# ANIMA_Small_Scale.net
KiCad netlist of a schematic drawn in EAGLE
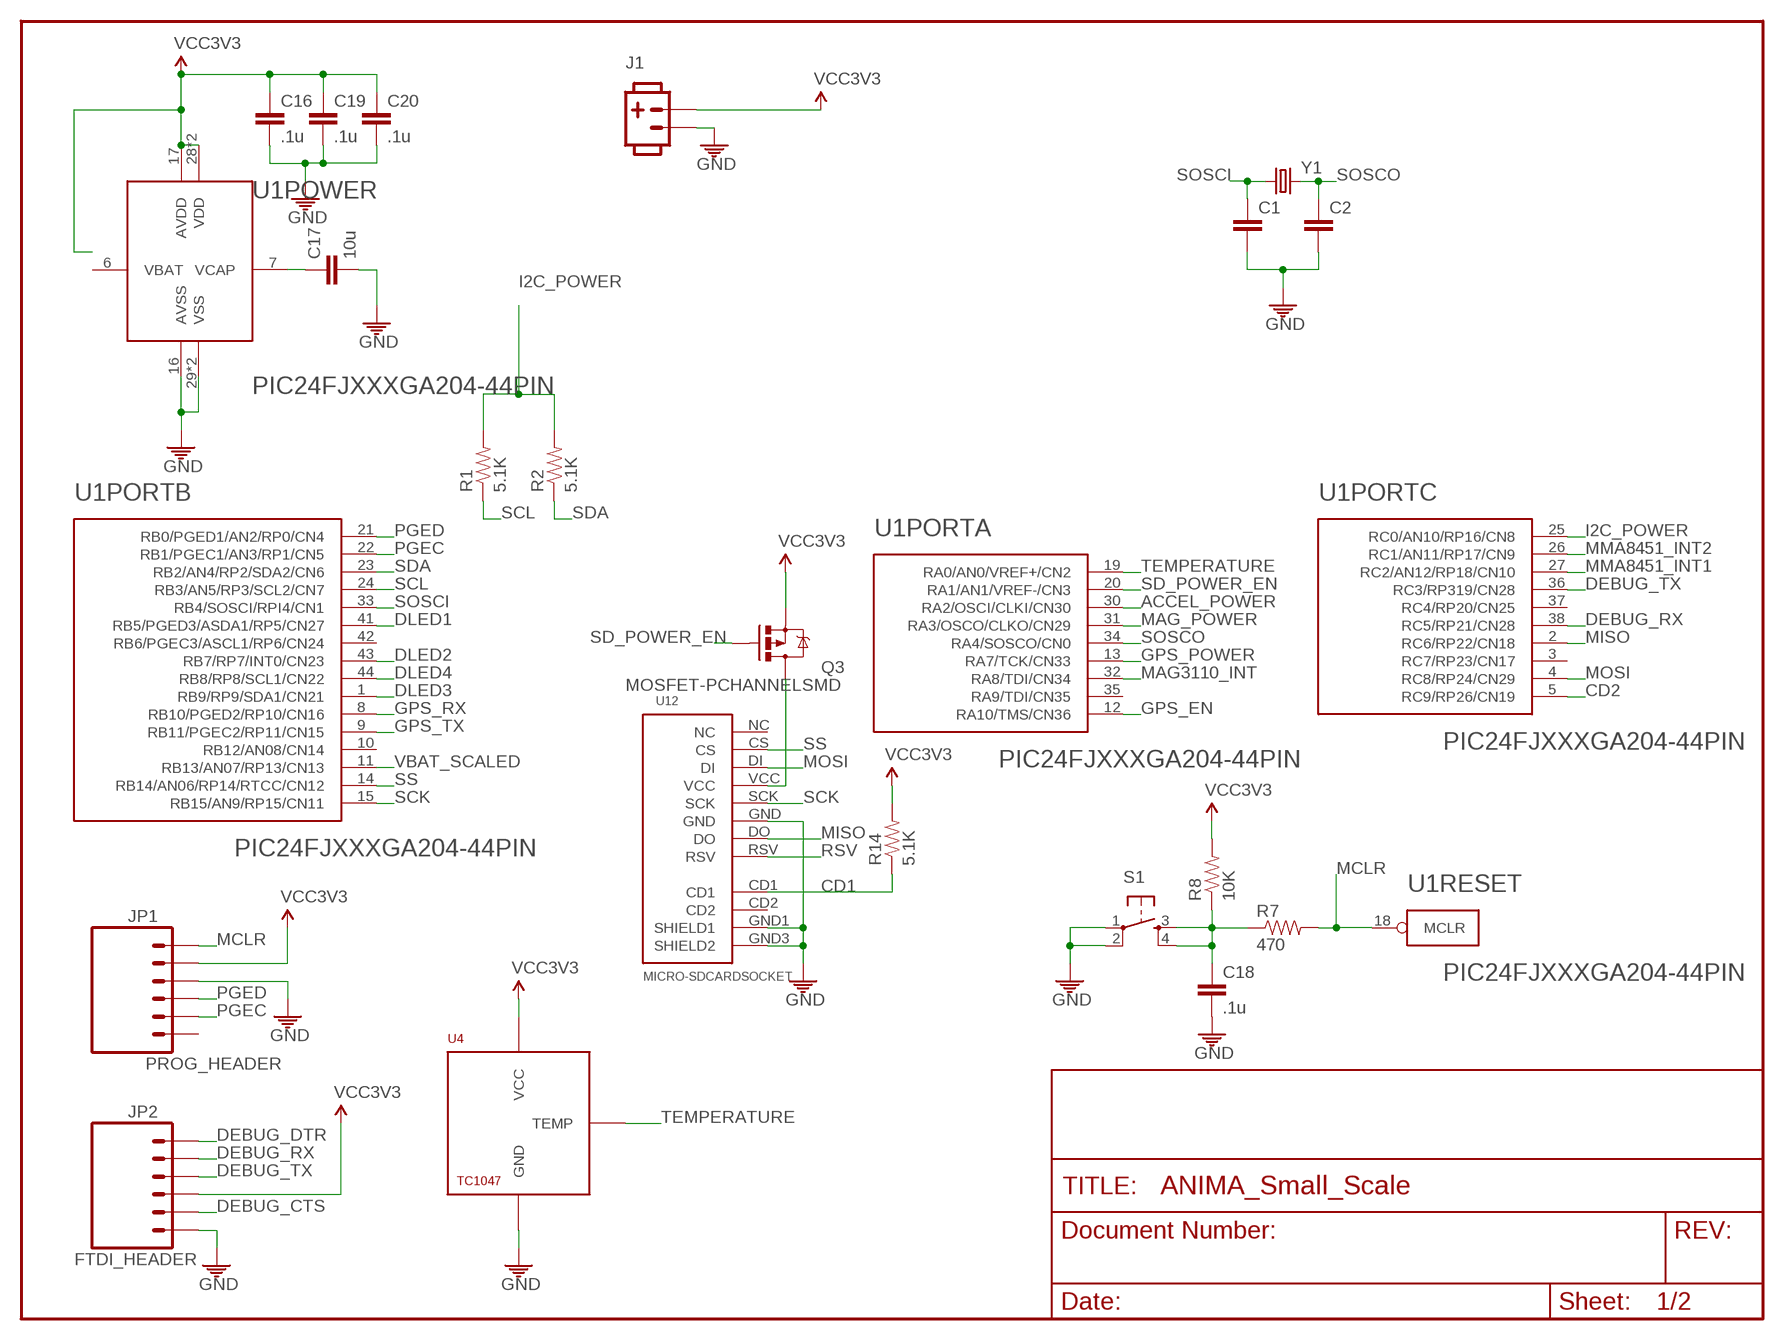
[diagram p0: schematic, sheet 1]
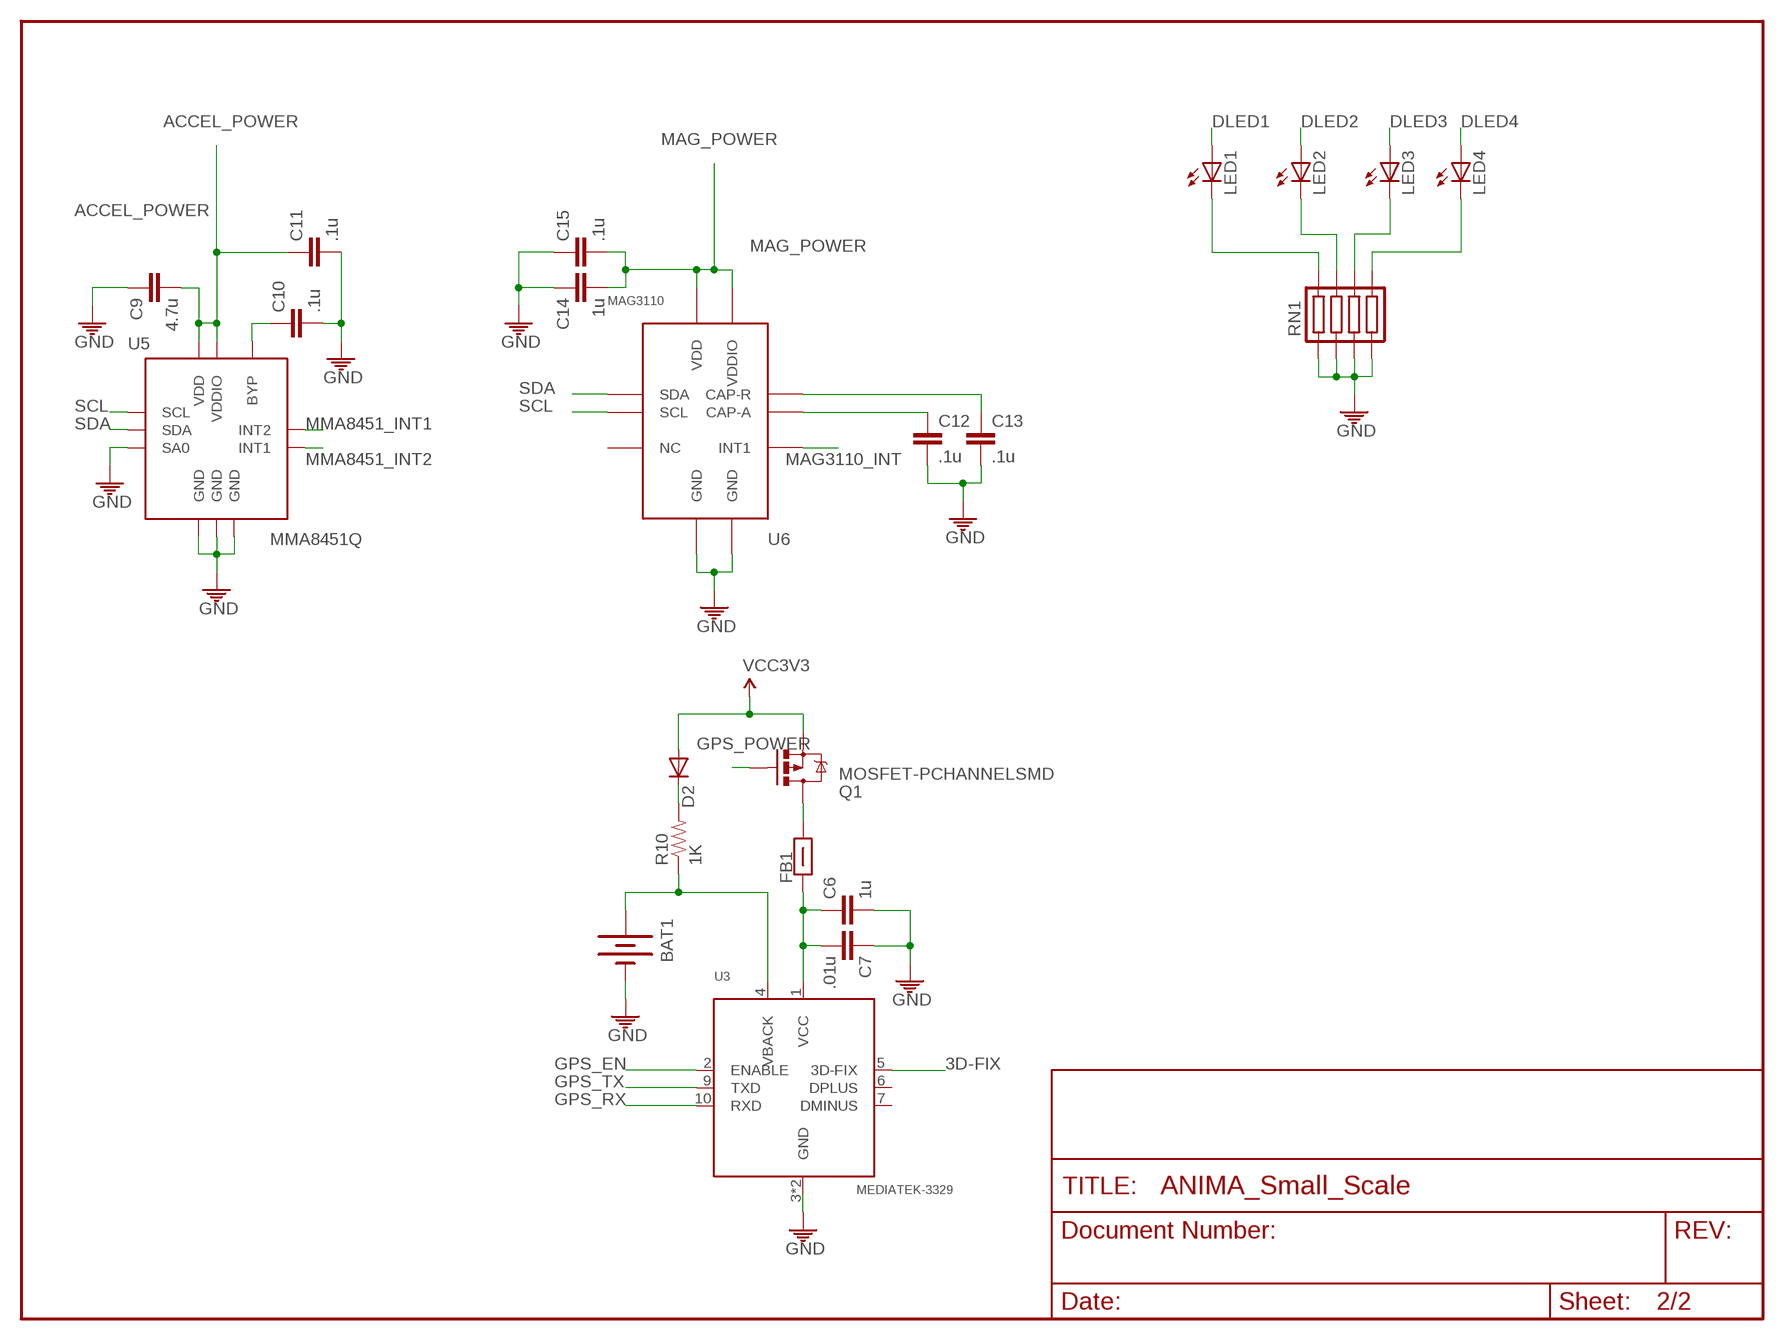
[diagram p1: schematic, sheet 2]

(export (version "E")
  (design (tool "Eeschema 10.0.6"))
  (components
    (comp (ref "BAT1")
      (value "BATTERY4.8MMSMD")
      (footprint "eagle-import:MS412FE-FL26E")
      (libsource (lib "eagle-import") (part "BATTERY4.8MMSMD"))
    )
    (comp (ref "C6")
      (value "1u")
      (footprint "eagle-import:0805")
      (libsource (lib "eagle-import") (part "CAP0805"))
    )
    (comp (ref "C7")
      (value ".01u")
      (footprint "eagle-import:0805")
      (libsource (lib "eagle-import") (part "CAP0805"))
    )
    (comp (ref "C9")
      (value "4.7u")
      (footprint "eagle-import:0805")
      (libsource (lib "eagle-import") (part "CAP0805"))
    )
    (comp (ref "C10")
      (value ".1u")
      (footprint "eagle-import:0805")
      (libsource (lib "eagle-import") (part "CAP0805"))
    )
    (comp (ref "C11")
      (value ".1u")
      (footprint "eagle-import:0805")
      (libsource (lib "eagle-import") (part "CAP0805"))
    )
    (comp (ref "C12")
      (value ".1u")
      (footprint "eagle-import:0805")
      (libsource (lib "eagle-import") (part "CAP0805"))
    )
    (comp (ref "C13")
      (value ".1u")
      (footprint "eagle-import:0805")
      (libsource (lib "eagle-import") (part "CAP0805"))
    )
    (comp (ref "C14")
      (value "1u")
      (footprint "eagle-import:0805")
      (libsource (lib "eagle-import") (part "CAP0805"))
    )
    (comp (ref "C15")
      (value ".1u")
      (footprint "eagle-import:0805")
      (libsource (lib "eagle-import") (part "CAP0805"))
    )
    (comp (ref "D2")
      (value "DIODESMA")
      (footprint "eagle-import:SMA-DIODE")
      (libsource (lib "eagle-import") (part "DIODESMA"))
    )
    (comp (ref "FB1")
      (value "FERRITE_BEAD")
      (footprint "eagle-import:0603")
      (libsource (lib "eagle-import") (part "FERRITE_BEAD"))
    )
    (comp (ref "LED1")
      (value "LED1206")
      (footprint "eagle-import:LED-1206")
      (libsource (lib "eagle-import") (part "LED1206"))
    )
    (comp (ref "LED2")
      (value "LED1206")
      (footprint "eagle-import:LED-1206")
      (libsource (lib "eagle-import") (part "LED1206"))
    )
    (comp (ref "LED3")
      (value "LED1206")
      (footprint "eagle-import:LED-1206")
      (libsource (lib "eagle-import") (part "LED1206"))
    )
    (comp (ref "LED4")
      (value "LED1206")
      (footprint "eagle-import:LED-1206")
      (libsource (lib "eagle-import") (part "LED1206"))
    )
    (comp (ref "Q1")
      (value "MOSFET-PCHANNELSMD")
      (footprint "eagle-import:SOT23-3")
      (libsource (lib "eagle-import") (part "MOSFET-PCHANNELSMD"))
    )
    (comp (ref "R10")
      (value "1K")
      (footprint "eagle-import:0805")
      (libsource (lib "eagle-import") (part "RESISTOR0805-RES"))
    )
    (comp (ref "RN1")
      (value "RESISTOR_ARRAY-4")
      (footprint "eagle-import:EXB-38V271JV")
      (libsource (lib "eagle-import") (part "RESISTOR_ARRAY-4"))
    )
    (comp (ref "U3")
      (value "MEDIATEK-3329")
      (footprint "eagle-import:MEDIATEK-3329")
      (libsource (lib "eagle-import") (part "MEDIATEK-3329"))
    )
    (comp (ref "U5")
      (value "MMA8451Q")
      (footprint "eagle-import:QFN-16_FREE")
      (libsource (lib "eagle-import") (part "MMA8451Q"))
    )
    (comp (ref "U6")
      (value "MAG3110")
      (footprint "eagle-import:DFN-10_FREE")
      (libsource (lib "eagle-import") (part "MAG3110"))
    )
    (comp (ref "C1")
      (value "CAP0805")
      (footprint "eagle-import:0805")
      (libsource (lib "eagle-import") (part "CAP0805"))
    )
    (comp (ref "C2")
      (value "CAP0805")
      (footprint "eagle-import:0805")
      (libsource (lib "eagle-import") (part "CAP0805"))
    )
    (comp (ref "C16")
      (value ".1u")
      (footprint "eagle-import:0805")
      (libsource (lib "eagle-import") (part "CAP0805"))
    )
    (comp (ref "C17")
      (value "10u")
      (footprint "eagle-import:0805")
      (libsource (lib "eagle-import") (part "CAP0805"))
    )
    (comp (ref "C18")
      (value ".1u")
      (footprint "eagle-import:0805")
      (libsource (lib "eagle-import") (part "CAP0805"))
    )
    (comp (ref "C19")
      (value ".1u")
      (footprint "eagle-import:0805")
      (libsource (lib "eagle-import") (part "CAP0805"))
    )
    (comp (ref "C20")
      (value ".1u")
      (footprint "eagle-import:0805")
      (libsource (lib "eagle-import") (part "CAP0805"))
    )
    (comp (ref "J1")
      (value "POW_CONNECTFEMALE-RA")
      (footprint "eagle-import:SOCKET-FEMALE_RA-3.96MM-2")
      (libsource (lib "eagle-import") (part "POW_CONNECTFEMALE-RA"))
    )
    (comp (ref "JP1")
      (value "M06FEMALE_LOCK")
      (footprint "eagle-import:1X06_FEMALE_LOCK.010")
      (libsource (lib "eagle-import") (part "M06FEMALE_LOCK"))
    )
    (comp (ref "JP2")
      (value "M06FEMALE_LOCK")
      (footprint "eagle-import:1X06_FEMALE_LOCK.010")
      (libsource (lib "eagle-import") (part "M06FEMALE_LOCK"))
    )
    (comp (ref "Q3")
      (value "MOSFET-PCHANNELSMD")
      (footprint "eagle-import:SOT23-3")
      (libsource (lib "eagle-import") (part "MOSFET-PCHANNELSMD"))
    )
    (comp (ref "R1")
      (value "5.1K")
      (footprint "eagle-import:0805")
      (libsource (lib "eagle-import") (part "RESISTOR0805-RES"))
    )
    (comp (ref "R2")
      (value "5.1K")
      (footprint "eagle-import:0805")
      (libsource (lib "eagle-import") (part "RESISTOR0805-RES"))
    )
    (comp (ref "R7")
      (value "470")
      (footprint "eagle-import:0805")
      (libsource (lib "eagle-import") (part "RESISTOR0805-RES"))
    )
    (comp (ref "R8")
      (value "10K")
      (footprint "eagle-import:0805")
      (libsource (lib "eagle-import") (part "RESISTOR0805-RES"))
    )
    (comp (ref "R14")
      (value "5.1K")
      (footprint "eagle-import:0805")
      (libsource (lib "eagle-import") (part "RESISTOR0805-RES"))
    )
    (comp (ref "S1")
      (value "TAC_SWITCHPTH")
      (footprint "eagle-import:B3F-1020")
      (libsource (lib "eagle-import") (part "TAC_SWITCHPTH"))
    )
    (comp (ref "U1")
      (value "PIC24FJXXXGA204-44PIN")
      (footprint "eagle-import:TQFP44")
      (libsource (lib "eagle-import") (part "PIC24FJXXXGA204-44PIN"))
    )
    (comp (ref "U4")
      (value "TC1047")
      (footprint "eagle-import:SOT-23B")
      (libsource (lib "eagle-import") (part "TC1047"))
    )
    (comp (ref "U12")
      (value "MICRO-SDCARDSOCKET")
      (footprint "eagle-import:MICRO-SD-SOCKET-PP")
      (libsource (lib "eagle-import") (part "MICRO-SDCARDSOCKET"))
    )
    (comp (ref "Y1")
      (value "CRYSTALABS07")
      (footprint "eagle-import:CRYSTAL-ABS07")
      (libsource (lib "eagle-import") (part "CRYSTALABS07"))
    )
  )
  (nets
    (net (code "1") (name "3D-FIX") (class "Default")
      (node (ref "U3") (pin "5") (pinfunction "3D-FIX_5") (pintype "output"))
    )
    (net (code "2") (name "ACCEL_POWER") (class "Default")
      (node (ref "C11") (pin "1") (pinfunction "1_1") (pintype "passive"))
      (node (ref "C9") (pin "2") (pinfunction "2_2") (pintype "passive"))
      (node (ref "U1") (pin "30") (pinfunction "RA2/OSCI/CLKI/CN30_30") (pintype "bidirectional"))
      (node (ref "U5") (pin "P$1") (pinfunction "VDDIO_P$1") (pintype "passive"))
      (node (ref "U5") (pin "P$14") (pinfunction "VDD_P$14") (pintype "passive"))
    )
    (net (code "3") (name "CD1") (class "Default")
      (node (ref "R14") (pin "1") (pinfunction "1_1") (pintype "passive"))
      (node (ref "U12") (pin "CD1") (pinfunction "CD1_CD1") (pintype "bidirectional"))
    )
    (net (code "4") (name "CD2") (class "Default")
      (node (ref "U1") (pin "5") (pinfunction "RC9/RP26/CN19_5") (pintype "bidirectional"))
    )
    (net (code "5") (name "DEBUG_CTS") (class "Default")
      (node (ref "JP2") (pin "5") (pinfunction "5_5") (pintype "passive"))
    )
    (net (code "6") (name "DEBUG_DTR") (class "Default")
      (node (ref "JP2") (pin "1") (pinfunction "1_1") (pintype "passive"))
    )
    (net (code "7") (name "DEBUG_RX") (class "Default")
      (node (ref "JP2") (pin "2") (pinfunction "2_2") (pintype "passive"))
      (node (ref "U1") (pin "38") (pinfunction "RC5/RP21/CN28_38") (pintype "bidirectional"))
    )
    (net (code "8") (name "DEBUG_TX") (class "Default")
      (node (ref "JP2") (pin "3") (pinfunction "3_3") (pintype "passive"))
      (node (ref "U1") (pin "36") (pinfunction "RC3/RP319/CN28_36") (pintype "bidirectional"))
    )
    (net (code "9") (name "DLED1") (class "Default")
      (node (ref "LED1") (pin "A") (pinfunction "A_A") (pintype "passive"))
      (node (ref "U1") (pin "41") (pinfunction "RB5/PGED3/ASDA1/RP5/CN27_41") (pintype "bidirectional"))
    )
    (net (code "10") (name "DLED2") (class "Default")
      (node (ref "LED2") (pin "A") (pinfunction "A_A") (pintype "passive"))
      (node (ref "U1") (pin "43") (pinfunction "RB7/RP7/INT0/CN23_43") (pintype "bidirectional"))
    )
    (net (code "11") (name "DLED3") (class "Default")
      (node (ref "LED3") (pin "A") (pinfunction "A_A") (pintype "passive"))
      (node (ref "U1") (pin "1") (pinfunction "RB9/RP9/SDA1/CN21_1") (pintype "bidirectional"))
    )
    (net (code "12") (name "DLED4") (class "Default")
      (node (ref "LED4") (pin "A") (pinfunction "A_A") (pintype "passive"))
      (node (ref "U1") (pin "44") (pinfunction "RB8/RP8/SCL1/CN22_44") (pintype "bidirectional"))
    )
    (net (code "13") (name "GND") (class "Default")
      (node (ref "BAT1") (pin "-") (pinfunction "-_-") (pintype "power_in"))
      (node (ref "C1") (pin "2") (pinfunction "2_2") (pintype "passive"))
      (node (ref "C10") (pin "2") (pinfunction "2_2") (pintype "passive"))
      (node (ref "C11") (pin "2") (pinfunction "2_2") (pintype "passive"))
      (node (ref "C12") (pin "2") (pinfunction "2_2") (pintype "passive"))
      (node (ref "C13") (pin "2") (pinfunction "2_2") (pintype "passive"))
      (node (ref "C14") (pin "1") (pinfunction "1_1") (pintype "passive"))
      (node (ref "C15") (pin "1") (pinfunction "1_1") (pintype "passive"))
      (node (ref "C16") (pin "2") (pinfunction "2_2") (pintype "passive"))
      (node (ref "C17") (pin "2") (pinfunction "2_2") (pintype "passive"))
      (node (ref "C18") (pin "2") (pinfunction "2_2") (pintype "passive"))
      (node (ref "C19") (pin "2") (pinfunction "2_2") (pintype "passive"))
      (node (ref "C2") (pin "2") (pinfunction "2_2") (pintype "passive"))
      (node (ref "C20") (pin "2") (pinfunction "2_2") (pintype "passive"))
      (node (ref "C6") (pin "2") (pinfunction "2_2") (pintype "passive"))
      (node (ref "C7") (pin "1") (pinfunction "1_1") (pintype "passive"))
      (node (ref "C9") (pin "1") (pinfunction "1_1") (pintype "passive"))
      (node (ref "J1") (pin "2") (pinfunction "2_2") (pintype "passive"))
      (node (ref "JP1") (pin "3") (pinfunction "3_3") (pintype "passive"))
      (node (ref "JP2") (pin "6") (pinfunction "6_6") (pintype "passive"))
      (node (ref "RN1") (pin "P$1") (pinfunction "1_P$1") (pintype "passive"))
      (node (ref "RN1") (pin "P$2") (pinfunction "2_P$2") (pintype "passive"))
      (node (ref "RN1") (pin "P$3") (pinfunction "3_P$3") (pintype "passive"))
      (node (ref "RN1") (pin "P$4") (pinfunction "4_P$4") (pintype "passive"))
      (node (ref "S1") (pin "1") (pinfunction "1_1") (pintype "passive"))
      (node (ref "S1") (pin "2") (pinfunction "2_2") (pintype "passive"))
      (node (ref "U1") (pin "16") (pinfunction "AVSS_16") (pintype "bidirectional"))
      (node (ref "U1") (pin "29") (pinfunction "VSS_29") (pintype "bidirectional"))
      (node (ref "U1") (pin "39") (pinfunction "VSS_39") (pintype "bidirectional"))
      (node (ref "U12") (pin "GND") (pinfunction "GND_GND") (pintype "bidirectional"))
      (node (ref "U12") (pin "GND1") (pinfunction "SHIELD1_GND1") (pintype "bidirectional"))
      (node (ref "U12") (pin "GND3") (pinfunction "SHIELD2_GND3") (pintype "bidirectional"))
      (node (ref "U3") (pin "3") (pinfunction "GND_3") (pintype "power_in"))
      (node (ref "U3") (pin "8") (pinfunction "GND_8") (pintype "power_in"))
      (node (ref "U4") (pin "P$3") (pinfunction "GND_P$3") (pintype "power_in"))
      (node (ref "U5") (pin "P$10") (pinfunction "GND_P$10") (pintype "passive"))
      (node (ref "U5") (pin "P$12") (pinfunction "GND_P$12") (pintype "passive"))
      (node (ref "U5") (pin "P$5") (pinfunction "GND_P$5") (pintype "passive"))
      (node (ref "U5") (pin "P$7") (pinfunction "SA0_P$7") (pintype "bidirectional"))
      (node (ref "U6") (pin "P$10") (pinfunction "GND_P$10") (pintype "passive"))
      (node (ref "U6") (pin "P$5") (pinfunction "GND_P$5") (pintype "passive"))
    )
    (net (code "14") (name "GPS_EN") (class "Default")
      (node (ref "U1") (pin "12") (pinfunction "RA10/TMS/CN36_12") (pintype "bidirectional"))
      (node (ref "U3") (pin "2") (pinfunction "ENABLE_2") (pintype "input"))
    )
    (net (code "15") (name "GPS_POWER") (class "Default")
      (node (ref "Q1") (pin "1") (pinfunction "G_1") (pintype "passive"))
      (node (ref "U1") (pin "13") (pinfunction "RA7/TCK/CN33_13") (pintype "bidirectional"))
    )
    (net (code "16") (name "GPS_RX") (class "Default")
      (node (ref "U1") (pin "8") (pinfunction "RB10/PGED2/RP10/CN16_8") (pintype "bidirectional"))
      (node (ref "U3") (pin "10") (pinfunction "RXD_10") (pintype "input"))
    )
    (net (code "17") (name "GPS_TX") (class "Default")
      (node (ref "U1") (pin "9") (pinfunction "RB11/PGEC2/RP11/CN15_9") (pintype "bidirectional"))
      (node (ref "U3") (pin "9") (pinfunction "TXD_9") (pintype "output"))
    )
    (net (code "18") (name "I2C_POWER") (class "Default")
      (node (ref "R1") (pin "2") (pinfunction "2_2") (pintype "passive"))
      (node (ref "R2") (pin "2") (pinfunction "2_2") (pintype "passive"))
      (node (ref "U1") (pin "25") (pinfunction "RC0/AN10/RP16/CN8_25") (pintype "bidirectional"))
    )
    (net (code "19") (name "MAG3110_INT") (class "Default")
      (node (ref "U1") (pin "32") (pinfunction "RA8/TDI/CN34_32") (pintype "bidirectional"))
      (node (ref "U6") (pin "P$9") (pinfunction "INT1_P$9") (pintype "passive"))
    )
    (net (code "20") (name "MAG_POWER") (class "Default")
      (node (ref "C14") (pin "2") (pinfunction "2_2") (pintype "passive"))
      (node (ref "C15") (pin "2") (pinfunction "2_2") (pintype "passive"))
      (node (ref "U1") (pin "31") (pinfunction "RA3/OSCO/CLKO/CN29_31") (pintype "bidirectional"))
      (node (ref "U6") (pin "P$2") (pinfunction "VDD_P$2") (pintype "passive"))
      (node (ref "U6") (pin "P$8") (pinfunction "VDDIO_P$8") (pintype "passive"))
    )
    (net (code "21") (name "MCLR") (class "Default")
      (node (ref "JP1") (pin "1") (pinfunction "1_1") (pintype "passive"))
      (node (ref "R7") (pin "2") (pinfunction "2_2") (pintype "passive"))
      (node (ref "U1") (pin "18") (pinfunction "MCLR_18") (pintype "bidirectional"))
    )
    (net (code "22") (name "MISO") (class "Default")
      (node (ref "U1") (pin "2") (pinfunction "RC6/RP22/CN18_2") (pintype "bidirectional"))
      (node (ref "U12") (pin "DO") (pinfunction "DO_DO") (pintype "bidirectional"))
    )
    (net (code "23") (name "MMA8451_INT1") (class "Default")
      (node (ref "U1") (pin "27") (pinfunction "RC2/AN12/RP18/CN10_27") (pintype "bidirectional"))
      (node (ref "U5") (pin "P$9") (pinfunction "INT2_P$9") (pintype "bidirectional"))
    )
    (net (code "24") (name "MMA8451_INT2") (class "Default")
      (node (ref "U1") (pin "26") (pinfunction "RC1/AN11/RP17/CN9_26") (pintype "bidirectional"))
      (node (ref "U5") (pin "P$11") (pinfunction "INT1_P$11") (pintype "bidirectional"))
    )
    (net (code "25") (name "MOSI") (class "Default")
      (node (ref "U1") (pin "4") (pinfunction "RC8/RP24/CN29_4") (pintype "bidirectional"))
      (node (ref "U12") (pin "DI") (pinfunction "DI_DI") (pintype "bidirectional"))
    )
    (net (code "26") (name "Net-(C18-Pad1)") (class "Default")
      (node (ref "C18") (pin "1") (pinfunction "1_1") (pintype "passive"))
      (node (ref "R7") (pin "1") (pinfunction "1_1") (pintype "passive"))
      (node (ref "R8") (pin "1") (pinfunction "1_1") (pintype "passive"))
      (node (ref "S1") (pin "3") (pinfunction "3_3") (pintype "passive"))
      (node (ref "S1") (pin "4") (pinfunction "4_4") (pintype "passive"))
    )
    (net (code "27") (name "Net-(D2-PadC)") (class "Default")
      (node (ref "D2") (pin "C") (pinfunction "C_C") (pintype "passive"))
      (node (ref "R10") (pin "2") (pinfunction "2_2") (pintype "passive"))
    )
    (net (code "28") (name "Net-(Q1-D)") (class "Default")
      (node (ref "FB1") (pin "2") (pinfunction "2_2") (pintype "passive"))
      (node (ref "Q1") (pin "3") (pinfunction "D_3") (pintype "passive"))
    )
    (net (code "29") (name "Net-(Q3-D)") (class "Default")
      (node (ref "Q3") (pin "3") (pinfunction "D_3") (pintype "passive"))
      (node (ref "U12") (pin "VCC") (pinfunction "VCC_VCC") (pintype "bidirectional"))
    )
    (net (code "30") (name "Net-(RN1-5)") (class "Default")
      (node (ref "LED4") (pin "C") (pinfunction "C_C") (pintype "passive"))
      (node (ref "RN1") (pin "P$5") (pinfunction "5_P$5") (pintype "passive"))
    )
    (net (code "31") (name "Net-(RN1-6)") (class "Default")
      (node (ref "LED3") (pin "C") (pinfunction "C_C") (pintype "passive"))
      (node (ref "RN1") (pin "P$6") (pinfunction "6_P$6") (pintype "passive"))
    )
    (net (code "32") (name "Net-(RN1-7)") (class "Default")
      (node (ref "LED2") (pin "C") (pinfunction "C_C") (pintype "passive"))
      (node (ref "RN1") (pin "P$7") (pinfunction "7_P$7") (pintype "passive"))
    )
    (net (code "33") (name "Net-(RN1-8)") (class "Default")
      (node (ref "LED1") (pin "C") (pinfunction "C_C") (pintype "passive"))
      (node (ref "RN1") (pin "P$8") (pinfunction "8_P$8") (pintype "passive"))
    )
    (net (code "34") (name "Net-(U1D-VCAP)") (class "Default")
      (node (ref "C17") (pin "1") (pinfunction "1_1") (pintype "passive"))
      (node (ref "U1") (pin "7") (pinfunction "VCAP_7") (pintype "bidirectional"))
    )
    (net (code "35") (name "Net-(U3-VBACK)") (class "Default")
      (node (ref "BAT1") (pin "+") (pinfunction "+_+") (pintype "power_in"))
      (node (ref "R10") (pin "1") (pinfunction "1_1") (pintype "passive"))
      (node (ref "U3") (pin "4") (pinfunction "VBACK_4") (pintype "power_in"))
    )
    (net (code "36") (name "Net-(U3-VCC)") (class "Default")
      (node (ref "C6") (pin "1") (pinfunction "1_1") (pintype "passive"))
      (node (ref "C7") (pin "2") (pinfunction "2_2") (pintype "passive"))
      (node (ref "FB1") (pin "1") (pinfunction "1_1") (pintype "passive"))
      (node (ref "U3") (pin "1") (pinfunction "VCC_1") (pintype "power_in"))
    )
    (net (code "37") (name "Net-(U5-BYP)") (class "Default")
      (node (ref "C10") (pin "1") (pinfunction "1_1") (pintype "passive"))
      (node (ref "U5") (pin "P$2") (pinfunction "BYP_P$2") (pintype "bidirectional"))
    )
    (net (code "38") (name "Net-(U6-CAP-A)") (class "Default")
      (node (ref "C12") (pin "1") (pinfunction "1_1") (pintype "passive"))
      (node (ref "U6") (pin "P$1") (pinfunction "CAP-A_P$1") (pintype "passive"))
    )
    (net (code "39") (name "Net-(U6-CAP-R)") (class "Default")
      (node (ref "C13") (pin "1") (pinfunction "1_1") (pintype "passive"))
      (node (ref "U6") (pin "P$4") (pinfunction "CAP-R_P$4") (pintype "passive"))
    )
    (net (code "40") (name "PGEC") (class "Default")
      (node (ref "JP1") (pin "5") (pinfunction "5_5") (pintype "passive"))
      (node (ref "U1") (pin "22") (pinfunction "RB1/PGEC1/AN3/RP1/CN5_22") (pintype "bidirectional"))
    )
    (net (code "41") (name "PGED") (class "Default")
      (node (ref "JP1") (pin "4") (pinfunction "4_4") (pintype "passive"))
      (node (ref "U1") (pin "21") (pinfunction "RB0/PGED1/AN2/RP0/CN4_21") (pintype "bidirectional"))
    )
    (net (code "42") (name "RSV") (class "Default")
      (node (ref "U12") (pin "RSV") (pinfunction "RSV_RSV") (pintype "bidirectional"))
    )
    (net (code "43") (name "SCK") (class "Default")
      (node (ref "U1") (pin "15") (pinfunction "RB15/AN9/RP15/CN11_15") (pintype "bidirectional"))
      (node (ref "U12") (pin "SCK") (pinfunction "SCK_SCK") (pintype "bidirectional"))
    )
    (net (code "44") (name "SCL") (class "Default")
      (node (ref "R1") (pin "1") (pinfunction "1_1") (pintype "passive"))
      (node (ref "U1") (pin "24") (pinfunction "RB3/AN5/RP3/SCL2/CN7_24") (pintype "bidirectional"))
      (node (ref "U5") (pin "P$4") (pinfunction "SCL_P$4") (pintype "bidirectional"))
      (node (ref "U6") (pin "P$7") (pinfunction "SCL_P$7") (pintype "passive"))
    )
    (net (code "45") (name "SDA") (class "Default")
      (node (ref "R2") (pin "1") (pinfunction "1_1") (pintype "passive"))
      (node (ref "U1") (pin "23") (pinfunction "RB2/AN4/RP2/SDA2/CN6_23") (pintype "bidirectional"))
      (node (ref "U5") (pin "P$6") (pinfunction "SDA_P$6") (pintype "bidirectional"))
      (node (ref "U6") (pin "P$6") (pinfunction "SDA_P$6") (pintype "passive"))
    )
    (net (code "46") (name "SD_POWER_EN") (class "Default")
      (node (ref "Q3") (pin "1") (pinfunction "G_1") (pintype "passive"))
      (node (ref "U1") (pin "20") (pinfunction "RA1/AN1/VREF-/CN3_20") (pintype "bidirectional"))
    )
    (net (code "47") (name "SOSCI") (class "Default")
      (node (ref "C1") (pin "1") (pinfunction "1_1") (pintype "passive"))
      (node (ref "U1") (pin "33") (pinfunction "RB4/SOSCI/RPI4/CN1_33") (pintype "bidirectional"))
      (node (ref "Y1") (pin "P$1") (pinfunction "1_P$1") (pintype "passive"))
    )
    (net (code "48") (name "SOSCO") (class "Default")
      (node (ref "C2") (pin "1") (pinfunction "1_1") (pintype "passive"))
      (node (ref "U1") (pin "34") (pinfunction "RA4/SOSCO/CN0_34") (pintype "bidirectional"))
      (node (ref "Y1") (pin "P$2") (pinfunction "2_P$2") (pintype "passive"))
    )
    (net (code "49") (name "SS") (class "Default")
      (node (ref "U1") (pin "14") (pinfunction "RB14/AN06/RP14/RTCC/CN12_14") (pintype "bidirectional"))
      (node (ref "U12") (pin "CS") (pinfunction "CS_CS") (pintype "bidirectional"))
    )
    (net (code "50") (name "TEMPERATURE") (class "Default")
      (node (ref "U1") (pin "19") (pinfunction "RA0/AN0/VREF+/CN2_19") (pintype "bidirectional"))
      (node (ref "U4") (pin "P$2") (pinfunction "TEMP_P$2") (pintype "output"))
    )
    (net (code "51") (name "VBAT_SCALED") (class "Default")
      (node (ref "U1") (pin "11") (pinfunction "RB13/AN07/RP13/CN13_11") (pintype "bidirectional"))
    )
    (net (code "52") (name "VCC3V3") (class "Default")
      (node (ref "C16") (pin "1") (pinfunction "1_1") (pintype "passive"))
      (node (ref "C19") (pin "1") (pinfunction "1_1") (pintype "passive"))
      (node (ref "C20") (pin "1") (pinfunction "1_1") (pintype "passive"))
      (node (ref "D2") (pin "A") (pinfunction "A_A") (pintype "passive"))
      (node (ref "J1") (pin "1") (pinfunction "1_1") (pintype "passive"))
      (node (ref "JP1") (pin "2") (pinfunction "2_2") (pintype "passive"))
      (node (ref "JP2") (pin "4") (pinfunction "4_4") (pintype "passive"))
      (node (ref "Q1") (pin "2") (pinfunction "S_2") (pintype "passive"))
      (node (ref "Q3") (pin "2") (pinfunction "S_2") (pintype "passive"))
      (node (ref "R14") (pin "2") (pinfunction "2_2") (pintype "passive"))
      (node (ref "R8") (pin "2") (pinfunction "2_2") (pintype "passive"))
      (node (ref "U1") (pin "17") (pinfunction "AVDD_17") (pintype "bidirectional"))
      (node (ref "U1") (pin "28") (pinfunction "VDD_28") (pintype "bidirectional"))
      (node (ref "U1") (pin "40") (pinfunction "VDD_40") (pintype "bidirectional"))
      (node (ref "U4") (pin "P$1") (pinfunction "VCC_P$1") (pintype "power_in"))
    )
    (net (code "53") (name "unconnected-(JP1-Pad6)") (class "Default")
      (node (ref "JP1") (pin "6") (pinfunction "6_6") (pintype "passive"))
    )
    (net (code "54") (name "unconnected-(U1A-RA9{slash}TDI{slash}CN35-Pad35)") (class "Default")
      (node (ref "U1") (pin "35") (pinfunction "RA9/TDI/CN35_35") (pintype "bidirectional"))
    )
    (net (code "55") (name "unconnected-(U1B-RB6{slash}PGEC3{slash}ASCL1{slash}RP6{slash}CN24-Pad42)") (class "Default")
      (node (ref "U1") (pin "42") (pinfunction "RB6/PGEC3/ASCL1/RP6/CN24_42") (pintype "bidirectional"))
    )
    (net (code "56") (name "unconnected-(U1B-RB12{slash}AN08{slash}CN14-Pad10)") (class "Default")
      (node (ref "U1") (pin "10") (pinfunction "RB12/AN08/CN14_10") (pintype "bidirectional"))
    )
    (net (code "57") (name "unconnected-(U1C-RC4{slash}RP20{slash}CN25-Pad37)") (class "Default")
      (node (ref "U1") (pin "37") (pinfunction "RC4/RP20/CN25_37") (pintype "bidirectional"))
    )
    (net (code "58") (name "unconnected-(U1C-RC7{slash}RP23{slash}CN17-Pad3)") (class "Default")
      (node (ref "U1") (pin "3") (pinfunction "RC7/RP23/CN17_3") (pintype "bidirectional"))
    )
    (net (code "59") (name "unconnected-(U1D-VBAT-Pad6)") (class "Default")
      (node (ref "U1") (pin "6") (pinfunction "VBAT_6") (pintype "bidirectional"))
    )
    (net (code "60") (name "unconnected-(U3-DMINUS-Pad7)") (class "Default")
      (node (ref "U3") (pin "7") (pinfunction "DMINUS_7") (pintype "bidirectional"))
    )
    (net (code "61") (name "unconnected-(U3-DPLUS-Pad6)") (class "Default")
      (node (ref "U3") (pin "6") (pinfunction "DPLUS_6") (pintype "bidirectional"))
    )
    (net (code "62") (name "unconnected-(U6-NC-PadP$3)") (class "Default")
      (node (ref "U6") (pin "P$3") (pinfunction "NC_P$3") (pintype "passive"))
    )
    (net (code "63") (name "unconnected-(U12-PadCD2)") (class "Default")
      (node (ref "U12") (pin "CD2") (pinfunction "CD2_CD2") (pintype "bidirectional"))
    )
    (net (code "64") (name "unconnected-(U12-PadNC)") (class "Default")
      (node (ref "U12") (pin "NC") (pinfunction "NC_NC") (pintype "bidirectional"))
    )
  )
)
